# tritiled22.net
KiCad netlist of a schematic drawn in EAGLE
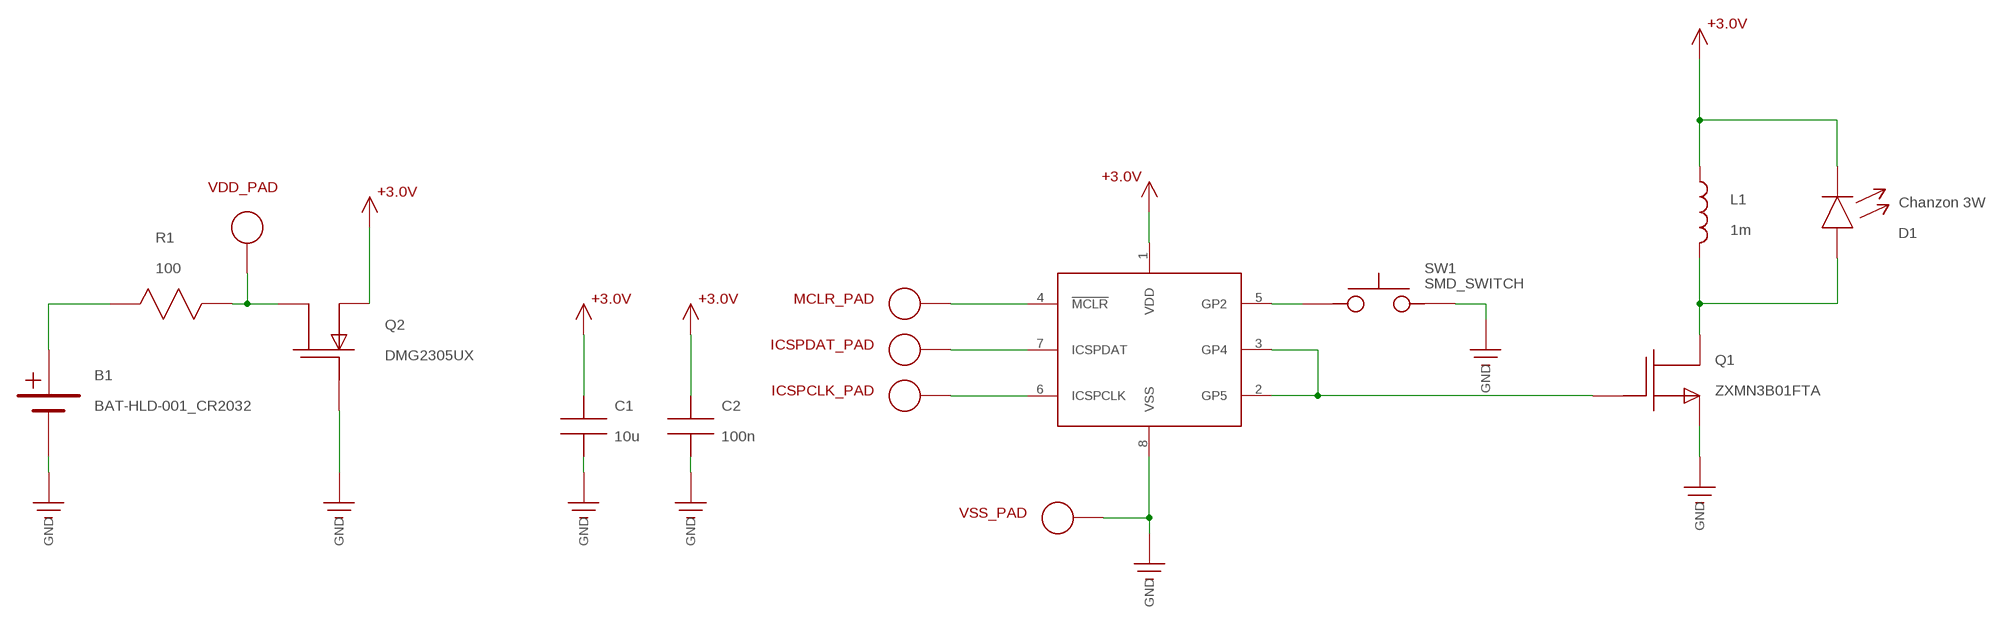
[diagram p0: schematic, sheet 1]

(export (version "E")
  (design (tool "Eeschema 10.0.6"))
  (components
    (comp (ref "B1")
      (value "BAT-HLD-001_CR2032")
      (footprint "eagle-import:CR2032_BAT-HLD_001")
      (libsource (lib "eagle-import") (part "BAT-HLD-001_CR2032"))
    )
    (comp (ref "C1")
      (value "10u")
      (footprint "eagle-import:1206")
      (libsource (lib "eagle-import") (part "C1206"))
    )
    (comp (ref "C2")
      (value "100n")
      (footprint "eagle-import:0805")
      (libsource (lib "eagle-import") (part "C0805"))
    )
    (comp (ref "D1")
      (value "Chanzon 3W")
      (footprint "eagle-import:LED_3W")
      (libsource (lib "eagle-import") (part "LED_3W"))
    )
    (comp (ref "ICSPCLK_PAD")
      (value "ICSP_PAD")
      (footprint "eagle-import:ICSP_PAD")
      (libsource (lib "eagle-import") (part "ICSP_PAD"))
    )
    (comp (ref "ICSPDAT_PAD")
      (value "ICSP_PAD")
      (footprint "eagle-import:ICSP_PAD")
      (libsource (lib "eagle-import") (part "ICSP_PAD"))
    )
    (comp (ref "L1")
      (value "1m")
      (footprint "eagle-import:SRR6028_INDUCTOR")
      (libsource (lib "eagle-import") (part "SRR6028_INDUCTOR"))
    )
    (comp (ref "MCLR_PAD")
      (value "ICSP_PAD")
      (footprint "eagle-import:ICSP_PAD")
      (libsource (lib "eagle-import") (part "ICSP_PAD"))
    )
    (comp (ref "Q1")
      (value "ZXMN3B01FTA")
      (footprint "eagle-import:SOT-23")
      (libsource (lib "eagle-import") (part "ZXMN3B01FSOT23"))
    )
    (comp (ref "Q2")
      (value "DMG2305UX")
      (footprint "eagle-import:SOT-23")
      (libsource (lib "eagle-import") (part "DMG2305UXSOT23"))
    )
    (comp (ref "R1")
      (value "100")
      (footprint "eagle-import:R1206")
      (libsource (lib "eagle-import") (part "R1206"))
    )
    (comp (ref "SW1")
      (value "SMD_SWITCH")
      (footprint "eagle-import:SMD_SWITCH")
      (libsource (lib "eagle-import") (part "SMD_SWITCH"))
    )
    (comp (ref "U1")
      (value "PIC12LF1571")
      (footprint "eagle-import:SOIC8")
      (libsource (lib "eagle-import") (part "PIC12LF1571"))
    )
    (comp (ref "VDD_PAD")
      (value "ICSP_PAD")
      (footprint "eagle-import:ICSP_PAD")
      (libsource (lib "eagle-import") (part "ICSP_PAD"))
    )
    (comp (ref "VSS_PAD")
      (value "ICSP_PAD")
      (footprint "eagle-import:ICSP_PAD")
      (libsource (lib "eagle-import") (part "ICSP_PAD"))
    )
  )
  (nets
    (net (code "1") (name "+3.0V") (class "Default")
      (node (ref "C1") (pin "P$1") (pinfunction "P$1_P$1") (pintype "bidirectional"))
      (node (ref "C2") (pin "P$1") (pinfunction "P$1_P$1") (pintype "bidirectional"))
      (node (ref "D1") (pin "C") (pinfunction "C_C") (pintype "bidirectional"))
      (node (ref "L1") (pin "P$1") (pinfunction "1_P$1") (pintype "passive"))
      (node (ref "Q2") (pin "2") (pinfunction "S_2") (pintype "bidirectional"))
      (node (ref "U1") (pin "1") (pinfunction "VDD_1") (pintype "bidirectional"))
    )
    (net (code "2") (name "GND") (class "Default")
      (node (ref "B1") (pin "GND") (pinfunction "0V_GND") (pintype "power_in"))
      (node (ref "C1") (pin "P$2") (pinfunction "P$2_P$2") (pintype "bidirectional"))
      (node (ref "C2") (pin "P$2") (pinfunction "P$2_P$2") (pintype "bidirectional"))
      (node (ref "Q1") (pin "2") (pinfunction "S_2") (pintype "bidirectional"))
      (node (ref "Q2") (pin "1") (pinfunction "G_1") (pintype "bidirectional"))
      (node (ref "SW1") (pin "P$3") (pinfunction "P$2_P$3") (pintype "bidirectional"))
      (node (ref "SW1") (pin "P$4") (pinfunction "P$2_P$4") (pintype "bidirectional"))
      (node (ref "U1") (pin "8") (pinfunction "VSS_8") (pintype "bidirectional"))
      (node (ref "VSS_PAD") (pin "P$2") (pinfunction "P$1_P$2") (pintype "bidirectional"))
    )
    (net (code "3") (name "Net-(B1-+V-Pad+V1)") (class "Default")
      (node (ref "B1") (pin "+V1") (pinfunction "+V_+V1") (pintype "power_in"))
      (node (ref "B1") (pin "+V2") (pinfunction "+V_+V2") (pintype "power_in"))
      (node (ref "R1") (pin "P$1") (pinfunction "P$1_P$1") (pintype "bidirectional"))
    )
    (net (code "4") (name "Net-(ICSPCLK_PAD-P$1)") (class "Default")
      (node (ref "ICSPCLK_PAD") (pin "P$2") (pinfunction "P$1_P$2") (pintype "bidirectional"))
      (node (ref "U1") (pin "6") (pinfunction "ICSPCLK_6") (pintype "bidirectional"))
    )
    (net (code "5") (name "Net-(ICSPDAT_PAD-P$1)") (class "Default")
      (node (ref "ICSPDAT_PAD") (pin "P$2") (pinfunction "P$1_P$2") (pintype "bidirectional"))
      (node (ref "U1") (pin "7") (pinfunction "ICSPDAT_7") (pintype "bidirectional"))
    )
    (net (code "6") (name "Net-(L1-2)") (class "Default")
      (node (ref "D1") (pin "A") (pinfunction "A_A") (pintype "bidirectional"))
      (node (ref "L1") (pin "P$2") (pinfunction "2_P$2") (pintype "passive"))
      (node (ref "Q1") (pin "3") (pinfunction "D_3") (pintype "bidirectional"))
    )
    (net (code "7") (name "Net-(MCLR_PAD-P$1)") (class "Default")
      (node (ref "MCLR_PAD") (pin "P$2") (pinfunction "P$1_P$2") (pintype "bidirectional"))
      (node (ref "U1") (pin "4") (pinfunction "~{MCLR}_4") (pintype "bidirectional"))
    )
    (net (code "8") (name "Net-(Q1-G)") (class "Default")
      (node (ref "Q1") (pin "1") (pinfunction "G_1") (pintype "bidirectional"))
      (node (ref "U1") (pin "2") (pinfunction "GP5_2") (pintype "bidirectional"))
      (node (ref "U1") (pin "3") (pinfunction "GP4_3") (pintype "bidirectional"))
    )
    (net (code "9") (name "Net-(Q2-D)") (class "Default")
      (node (ref "Q2") (pin "3") (pinfunction "D_3") (pintype "bidirectional"))
      (node (ref "R1") (pin "P$2") (pinfunction "P$2_P$2") (pintype "bidirectional"))
      (node (ref "VDD_PAD") (pin "P$2") (pinfunction "P$1_P$2") (pintype "bidirectional"))
    )
    (net (code "10") (name "Net-(U1-GP2)") (class "Default")
      (node (ref "SW1") (pin "P$1") (pinfunction "P$1_P$1") (pintype "bidirectional"))
      (node (ref "SW1") (pin "P$2") (pinfunction "P$1_P$2") (pintype "bidirectional"))
      (node (ref "U1") (pin "5") (pinfunction "GP2_5") (pintype "bidirectional"))
    )
  )
)
